# RS485.net
KiCad netlist of a schematic drawn in Altium Designer
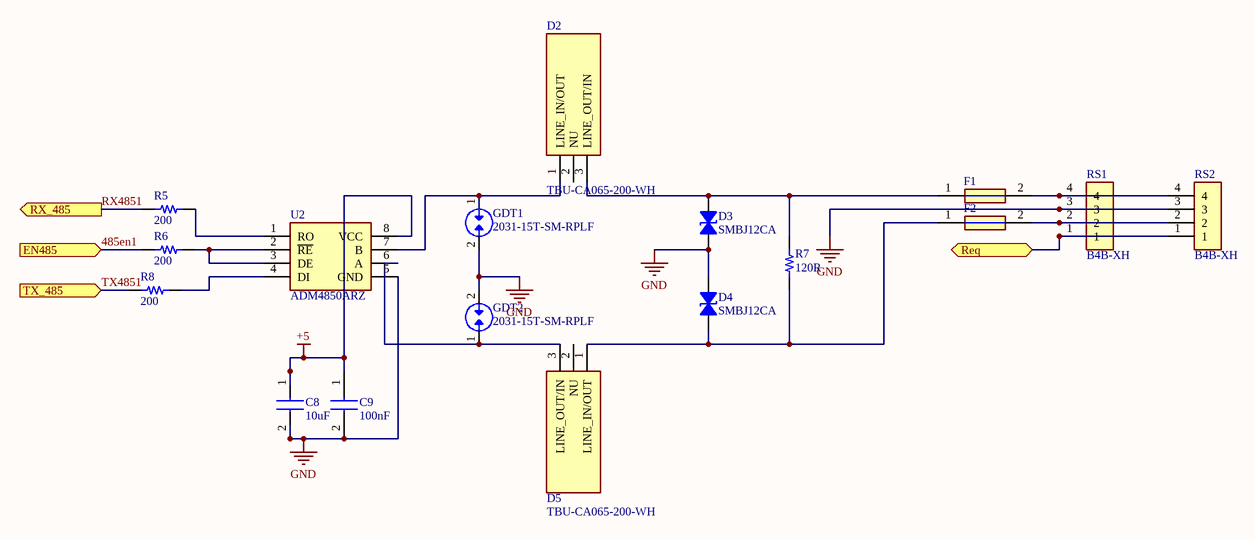
[diagram p0: RS485.SchDoc]

(export (version "E")
  (design (tool "Eeschema 10.0.6"))
  (components
    (comp (ref "C8")
      (value "10uF")
      (footprint "Cap1206_(3216X15L)")
      (description "CAP SMD 0603")
      (fields
        (field (name "MANUFACTURER_PART_NUMBER") "C1206C104Z5UACTU")
        (field (name "MOUSER PART NUMBER") "80-C1206C104Z5U")
      )
      (libsource (lib "*") (part "C1206C104Z5UACTU"))
    )
    (comp (ref "C9")
      (value "100nF")
      (footprint "Cap1206_(3216X15L)")
      (description "CAP SMD 0603")
      (fields
        (field (name "MANUFACTURER_PART_NUMBER") "C1206C104Z5UACTU")
        (field (name "MOUSER PART NUMBER") "80-C1206C104Z5U")
      )
      (libsource (lib "*") (part "C1206C104Z5UACTU"))
    )
    (comp (ref "D2")
      (value "TBU-CA065-200-WH")
      (footprint "TBUCA025050WH")
      (description "TVS Diode (Bi-directional)")
      (fields (field (name "MOUSER PART NUMBER") "652-TBU-CA065-200-WH"))
      (libsource (lib "*") (part "TBU-CA065-200-WH"))
    )
    (comp (ref "D3")
      (value "SMBJ12CA")
      (footprint "DO214AA SMB")
      (description "TVS DIODE 12V 19.9V SMB")
      (fields (field (name "MANUFACTURER") "AVX Corporation"))
      (libsource (lib "Celestial Altium Library - altium_library") (part "Diode TVS"))
    )
    (comp (ref "D4")
      (value "SMBJ12CA")
      (footprint "DO214AA SMB")
      (description "TVS DIODE 12V 19.9V SMB")
      (fields (field (name "MANUFACTURER") "AVX Corporation"))
      (libsource (lib "Celestial Altium Library - altium_library") (part "Diode TVS"))
    )
    (comp (ref "D5")
      (value "TBU-CA065-200-WH")
      (footprint "TBUCA025050WH")
      (description "TVS Diode (Bi-directional)")
      (fields (field (name "MOUSER PART NUMBER") "652-TBU-CA065-200-WH"))
      (libsource (lib "") (part "TBU-CA065-200-WH_1"))
    )
    (comp (ref "F1")
      (value "fuse 100mAmp")
      (footprint "1206 FUSE")
      (description "Fuse 1206")
      (fields (field (name "MANUFACTURER_PART_NUMBER") "1206SFS200F/63-2"))
      (libsource (lib "*") (part "1206SFS200F_63-2"))
    )
    (comp (ref "F2")
      (value "fuse 100mAmp")
      (footprint "1206 FUSE")
      (description "Fuse 1206")
      (fields (field (name "MANUFACTURER_PART_NUMBER") "1206SFS200F/63-2"))
      (libsource (lib "*") (part "1206SFS200F_63-2"))
    )
    (comp (ref "GDT1")
      (value "2031-15T-SM-RPLF")
      (footprint "TVS_2031-15T-SM-RPLF")
      (description "Gas Discharge Tube SMD")
      (libsource (lib "2031-15T-SM-RPLF") (part "2031-15T-SM-RPLF"))
    )
    (comp (ref "GDT2")
      (value "2031-15T-SM-RPLF")
      (footprint "TVS_2031-15T-SM-RPLF")
      (description "Gas Discharge Tube SMD")
      (libsource (lib "2031-15T-SM-RPLF") (part "2031-15T-SM-RPLF"))
    )
    (comp (ref "R5")
      (value "200")
      (footprint "0603R")
      (description "RES SMD 0603")
      (fields (field (name "PART NUMBER") "CRCW080510K0JNEAIF") (field (name "MANUFACTURER") "Vishay Dale"))
      (libsource (lib "Celestial Altium Library - altium_library") (part "Resistor"))
    )
    (comp (ref "R6")
      (value "200")
      (footprint "0603R")
      (description "RES SMD 0603")
      (fields (field (name "PART NUMBER") "CRCW080510K0JNEAIF") (field (name "MANUFACTURER") "Vishay Dale"))
      (libsource (lib "Celestial Altium Library - altium_library") (part "Resistor"))
    )
    (comp (ref "R7")
      (value "120R")
      (footprint "0603R")
      (description "RES SMD 0603")
      (fields (field (name "PART NUMBER") "CRCW080510K0JNEAIF") (field (name "MANUFACTURER") "Vishay Dale"))
      (libsource (lib "Celestial Altium Library - altium_library") (part "Resistor"))
    )
    (comp (ref "R8")
      (value "200")
      (footprint "0603R")
      (description "RES SMD 0603")
      (fields (field (name "PART NUMBER") "CRCW080510K0JNEAIF") (field (name "MANUFACTURER") "Vishay Dale"))
      (libsource (lib "Celestial Altium Library - altium_library") (part "Resistor"))
    )
    (comp (ref "RS1")
      (value "B4B-XH")
      (footprint "JST-B4B-XH")
      (description "XH 4pin standing")
      (libsource (lib "XHBBLIB") (part "B4B-XH"))
    )
    (comp (ref "RS2")
      (value "B4B-XH")
      (footprint "JST-B4B-XH")
      (description "XH 4pin standing")
      (libsource (lib "XHBBLIB") (part "B4B-XH"))
    )
    (comp (ref "U2")
      (value "ADM4850ARZ")
      (footprint "SO8_N")
      (description "MAX485 SMD")
      (fields (field (name "MOUSER PART NUMBER") "584-ADM4850ARZ"))
      (libsource (lib "*") (part "ADM4850ARZ"))
    )
  )
  (nets
    (net (code "1") (name "+5") (class "Default")
      (node (ref "C8") (pin "1") (pinfunction "1_1") (pintype "passive"))
      (node (ref "C9") (pin "1") (pinfunction "1_1") (pintype "passive"))
      (node (ref "U2") (pin "8") (pinfunction "VCC_8") (pintype "passive"))
    )
    (net (code "2") (name "/485en1") (class "Default")
      (node (ref "R6") (pin "2") (pinfunction "2_2") (pintype "passive"))
    )
    (net (code "3") (name "/RX4851") (class "Default")
      (node (ref "R5") (pin "2") (pinfunction "2_2") (pintype "passive"))
    )
    (net (code "4") (name "/Req") (class "Default")
      (node (ref "RS1") (pin "1") (pinfunction "1_1") (pintype "passive"))
      (node (ref "RS2") (pin "1") (pinfunction "1_1") (pintype "passive"))
    )
    (net (code "5") (name "/TX4851") (class "Default")
      (node (ref "R8") (pin "2") (pinfunction "2_2") (pintype "passive"))
    )
    (net (code "6") (name "GND") (class "Default")
      (node (ref "C8") (pin "2") (pinfunction "2_2") (pintype "passive"))
      (node (ref "C9") (pin "2") (pinfunction "2_2") (pintype "passive"))
      (node (ref "D3") (pin "1") (pinfunction "1_1") (pintype "passive"))
      (node (ref "D4") (pin "2") (pinfunction "2_2") (pintype "passive"))
      (node (ref "GDT1") (pin "2") (pinfunction "2_2") (pintype "passive"))
      (node (ref "GDT2") (pin "2") (pinfunction "2_2") (pintype "passive"))
      (node (ref "RS1") (pin "3") (pinfunction "3_3") (pintype "passive"))
      (node (ref "RS2") (pin "3") (pinfunction "3_3") (pintype "passive"))
      (node (ref "U2") (pin "5") (pinfunction "GND_5") (pintype "passive"))
    )
    (net (code "7") (name "Net-(D2-LINE_IN{slash}OUT)") (class "Default")
      (node (ref "D2") (pin "1") (pinfunction "LINE_IN/OUT_1") (pintype "passive"))
      (node (ref "GDT1") (pin "1") (pinfunction "1_1") (pintype "passive"))
      (node (ref "U2") (pin "7") (pinfunction "B_7") (pintype "passive"))
    )
    (net (code "8") (name "Net-(D2-LINE_OUT{slash}IN)") (class "Default")
      (node (ref "D2") (pin "3") (pinfunction "LINE_OUT/IN_3") (pintype "passive"))
      (node (ref "D3") (pin "2") (pinfunction "2_2") (pintype "passive"))
      (node (ref "F1") (pin "1") (pinfunction "1_1") (pintype "passive"))
      (node (ref "R7") (pin "1") (pinfunction "1_1") (pintype "passive"))
    )
    (net (code "9") (name "Net-(D5-LINE_IN{slash}OUT)") (class "Default")
      (node (ref "D4") (pin "1") (pinfunction "1_1") (pintype "passive"))
      (node (ref "D5") (pin "1") (pinfunction "LINE_IN/OUT_1") (pintype "passive"))
      (node (ref "F2") (pin "1") (pinfunction "1_1") (pintype "passive"))
      (node (ref "R7") (pin "2") (pinfunction "2_2") (pintype "passive"))
    )
    (net (code "10") (name "Net-(D5-LINE_OUT{slash}IN)") (class "Default")
      (node (ref "D5") (pin "3") (pinfunction "LINE_OUT/IN_3") (pintype "passive"))
      (node (ref "GDT2") (pin "1") (pinfunction "1_1") (pintype "passive"))
      (node (ref "U2") (pin "6") (pinfunction "A_6") (pintype "passive"))
    )
    (net (code "11") (name "Net-(F1-Pad2)") (class "Default")
      (node (ref "F1") (pin "2") (pinfunction "2_2") (pintype "passive"))
      (node (ref "RS1") (pin "4") (pinfunction "4_4") (pintype "passive"))
      (node (ref "RS2") (pin "4") (pinfunction "4_4") (pintype "passive"))
    )
    (net (code "12") (name "Net-(F2-Pad2)") (class "Default")
      (node (ref "F2") (pin "2") (pinfunction "2_2") (pintype "passive"))
      (node (ref "RS1") (pin "2") (pinfunction "2_2") (pintype "passive"))
      (node (ref "RS2") (pin "2") (pinfunction "2_2") (pintype "passive"))
    )
    (net (code "13") (name "Net-(U2-DE)") (class "Default")
      (node (ref "R6") (pin "1") (pinfunction "1_1") (pintype "passive"))
      (node (ref "U2") (pin "2") (pinfunction "~{RE}_2") (pintype "passive"))
      (node (ref "U2") (pin "3") (pinfunction "DE_3") (pintype "passive"))
    )
    (net (code "14") (name "Net-(U2-DI)") (class "Default")
      (node (ref "R8") (pin "1") (pinfunction "1_1") (pintype "passive"))
      (node (ref "U2") (pin "4") (pinfunction "DI_4") (pintype "passive"))
    )
    (net (code "15") (name "Net-(U2-RO)") (class "Default")
      (node (ref "R5") (pin "1") (pinfunction "1_1") (pintype "passive"))
      (node (ref "U2") (pin "1") (pinfunction "RO_1") (pintype "passive"))
    )
    (net (code "16") (name "unconnected-(D2-NU-Pad2)") (class "Default")
      (node (ref "D2") (pin "2") (pinfunction "NU_2") (pintype "passive"))
    )
    (net (code "17") (name "unconnected-(D5-NU-Pad2)") (class "Default")
      (node (ref "D5") (pin "2") (pinfunction "NU_2") (pintype "passive"))
    )
  )
)
